# SCH.net
KiCad netlist of a schematic drawn in Altium Designer
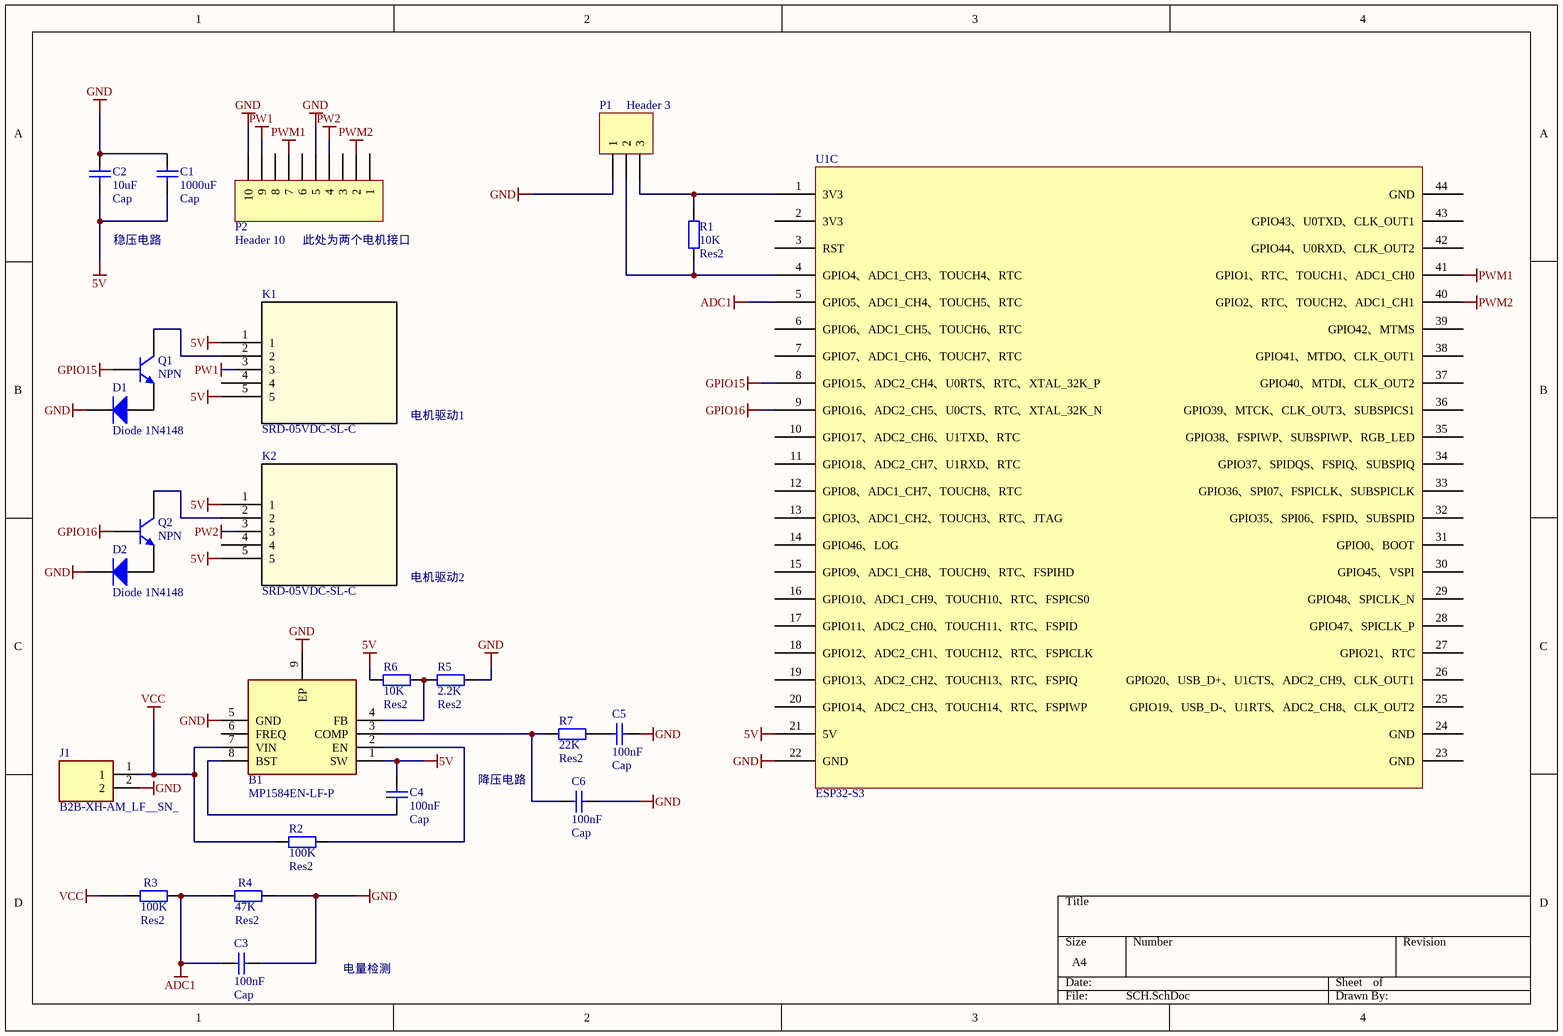
[diagram p0: SCH.SchDoc]

(export (version "E")
  (design (tool "Eeschema 10.0.6"))
  (components
    (comp (ref "B1")
      (value "MP1584EN-LF-P")
      (footprint "SOIC127P600X170-9N")
      (description "Switching Voltage Regulators NRFND: USE MP2338 as replacement")
      (fields (field (name "MOUSER PART NUMBER") "946-MP1584EN-LF-P"))
      (libsource (lib "MP1584EN-LF-P") (part "MP1584EN-LF-P"))
    )
    (comp (ref "C1")
      (value "Cap")
      (footprint "C0805")
      (description "Capacitor")
      (fields (field (name "ALTIUM_VALUE") "1000uF") (field (name "PUBLISHER") "Altium Limited"))
      (libsource (lib "Miscellaneous Devices") (part "Cap"))
    )
    (comp (ref "C2")
      (value "Cap")
      (footprint "C0805")
      (description "Capacitor")
      (fields (field (name "ALTIUM_VALUE") "10uF") (field (name "PUBLISHER") "Altium Limited"))
      (libsource (lib "Miscellaneous Devices") (part "Cap"))
    )
    (comp (ref "C3")
      (value "Cap")
      (footprint "C0805")
      (description "Capacitor")
      (fields (field (name "ALTIUM_VALUE") "100nF") (field (name "PUBLISHER") "Altium Limited"))
      (libsource (lib "Miscellaneous Devices") (part "Cap"))
    )
    (comp (ref "C4")
      (value "Cap")
      (footprint "C0805")
      (description "Capacitor")
      (fields (field (name "ALTIUM_VALUE") "100nF") (field (name "PUBLISHER") "Altium Limited"))
      (libsource (lib "Miscellaneous Devices") (part "Cap"))
    )
    (comp (ref "C5")
      (value "Cap")
      (footprint "C0805")
      (description "Capacitor")
      (fields (field (name "ALTIUM_VALUE") "100nF") (field (name "PUBLISHER") "Altium Limited"))
      (libsource (lib "Miscellaneous Devices") (part "Cap"))
    )
    (comp (ref "C6")
      (value "Cap")
      (footprint "C0805")
      (description "Capacitor")
      (fields (field (name "ALTIUM_VALUE") "100nF") (field (name "PUBLISHER") "Altium Limited"))
      (libsource (lib "Miscellaneous Devices") (part "Cap"))
    )
    (comp (ref "D1")
      (value "Diode 1N4148")
      (footprint "DO-35")
      (description "High Conductance Fast Diode")
      (fields (field (name "PUBLISHER") "Altium Limited"))
      (libsource (lib "Miscellaneous Devices") (part "Diode 1N4148"))
    )
    (comp (ref "D2")
      (value "Diode 1N4148")
      (footprint "DO-35")
      (description "High Conductance Fast Diode")
      (fields (field (name "PUBLISHER") "Altium Limited"))
      (libsource (lib "Miscellaneous Devices") (part "Diode 1N4148"))
    )
    (comp (ref "J1")
      (value "B2B-XH-AM_LF__SN_")
      (footprint "B2BXHAMLFSN")
      (description "CONN HEADER VERT 2POS 2.5MM")
      (fields
        (field (name "MANUFACTURER_PART_NUMBER") "B2B-XH-AM(LF)(SN)")
        (field (name "MOUSER PART NUMBER") "306-B2B-XH-AMLFSNP")
      )
      (libsource (lib "B2B-XH-AM_LF__SN_") (part "B2B-XH-AM_LF__SN_"))
    )
    (comp (ref "K1")
      (value "SRD-05VDC-SL-C")
      (footprint "RELAY_SRD-05VDC-SL-C_MCE")
      (description "Description")
      (fields (field (name "COPYRIGHT") "Copyright (C) 2026 Ultra Librarian. All rights reserved."))
      (libsource (lib "SRD-05VDC-SL-C") (part "SRD-05VDC-SL-C"))
    )
    (comp (ref "K2")
      (value "SRD-05VDC-SL-C")
      (footprint "RELAY_SRD-05VDC-SL-C_MCE")
      (description "Description")
      (fields (field (name "COPYRIGHT") "Copyright (C) 2026 Ultra Librarian. All rights reserved."))
      (libsource (lib "SRD-05VDC-SL-C") (part "SRD-05VDC-SL-C"))
    )
    (comp (ref "P1")
      (value "Header 3")
      (footprint "HDR1X3")
      (description "Header, 3-Pin")
      (fields (field (name "PUBLISHER") "Altium Limited"))
      (libsource (lib "Miscellaneous Connectors") (part "Header 3"))
    )
    (comp (ref "P2")
      (value "Header 10")
      (footprint "HDR1X10")
      (description "Header, 10-Pin")
      (fields (field (name "PUBLISHER") "Altium Limited"))
      (libsource (lib "Miscellaneous Connectors") (part "Header 10"))
    )
    (comp (ref "Q1")
      (value "NPN")
      (footprint "TO-226-AA")
      (description "NPN Bipolar Transistor")
      (fields (field (name "PUBLISHER") "Altium Limited"))
      (libsource (lib "Miscellaneous Devices") (part "NPN"))
    )
    (comp (ref "Q2")
      (value "NPN")
      (footprint "TO-226-AA")
      (description "NPN Bipolar Transistor")
      (fields (field (name "PUBLISHER") "Altium Limited"))
      (libsource (lib "Miscellaneous Devices") (part "NPN"))
    )
    (comp (ref "R1")
      (value "Res2")
      (footprint "C0805")
      (description "Resistor")
      (fields (field (name "ALTIUM_VALUE") "10K") (field (name "PUBLISHER") "Altium Limited"))
      (libsource (lib "") (part "Res2_2"))
    )
    (comp (ref "R2")
      (value "Res2")
      (footprint "C0805")
      (description "Resistor")
      (fields (field (name "ALTIUM_VALUE") "100K") (field (name "PUBLISHER") "Altium Limited"))
      (libsource (lib "") (part "Res2_1"))
    )
    (comp (ref "R3")
      (value "Res2")
      (footprint "C0805")
      (description "Resistor")
      (fields (field (name "ALTIUM_VALUE") "100K") (field (name "PUBLISHER") "Altium Limited"))
      (libsource (lib "") (part "Res2_1"))
    )
    (comp (ref "R4")
      (value "Res2")
      (footprint "C0805")
      (description "Resistor")
      (fields (field (name "ALTIUM_VALUE") "47K") (field (name "PUBLISHER") "Altium Limited"))
      (libsource (lib "") (part "Res2_1"))
    )
    (comp (ref "R5")
      (value "Res2")
      (footprint "C0805")
      (description "Resistor")
      (fields (field (name "ALTIUM_VALUE") "2.2K") (field (name "PUBLISHER") "Altium Limited"))
      (libsource (lib "") (part "Res2_1"))
    )
    (comp (ref "R6")
      (value "Res2")
      (footprint "C0805")
      (description "Resistor")
      (fields (field (name "ALTIUM_VALUE") "10K") (field (name "PUBLISHER") "Altium Limited"))
      (libsource (lib "Miscellaneous Devices") (part "Res2"))
    )
    (comp (ref "R7")
      (value "Res2")
      (footprint "C0805")
      (description "Resistor")
      (fields (field (name "ALTIUM_VALUE") "22K") (field (name "PUBLISHER") "Altium Limited"))
      (libsource (lib "Miscellaneous Devices") (part "Res2"))
    )
    (comp (ref "U1") (value "ESP32-S3") (footprint "ESP32-S3") (libsource (lib "Mylib") (part "ESP32-S3")))
  )
  (nets
    (net (code "1") (name "5V") (class "Default")
      (node (ref "B1") (pin "1") (pinfunction "SW_1") (pintype "passive"))
      (node (ref "C1") (pin "1") (pinfunction "1_1") (pintype "passive"))
      (node (ref "C2") (pin "1") (pinfunction "1_1") (pintype "passive"))
      (node (ref "C4") (pin "1") (pinfunction "1_1") (pintype "passive"))
      (node (ref "K1") (pin "1") (pinfunction "1_1") (pintype "passive"))
      (node (ref "K1") (pin "5") (pinfunction "5_5") (pintype "passive"))
      (node (ref "K2") (pin "1") (pinfunction "1_1") (pintype "passive"))
      (node (ref "K2") (pin "5") (pinfunction "5_5") (pintype "passive"))
      (node (ref "R6") (pin "2") (pinfunction "2_2") (pintype "passive"))
      (node (ref "U1") (pin "21") (pinfunction "5V_21") (pintype "passive"))
    )
    (net (code "2") (name "ADC1") (class "Default")
      (node (ref "C3") (pin "2") (pinfunction "2_2") (pintype "passive"))
      (node (ref "R3") (pin "2") (pinfunction "2_2") (pintype "passive"))
      (node (ref "R4") (pin "1") (pinfunction "1_1") (pintype "passive"))
      (node (ref "U1") (pin "5") (pinfunction "GPIO5、ADC1_CH4、TOUCH5、RTC_5") (pintype "passive"))
    )
    (net (code "3") (name "GND") (class "Default")
      (node (ref "B1") (pin "5") (pinfunction "GND_5") (pintype "passive"))
      (node (ref "B1") (pin "9") (pinfunction "EP_9") (pintype "passive"))
      (node (ref "C1") (pin "2") (pinfunction "2_2") (pintype "passive"))
      (node (ref "C2") (pin "2") (pinfunction "2_2") (pintype "passive"))
      (node (ref "C3") (pin "1") (pinfunction "1_1") (pintype "passive"))
      (node (ref "C5") (pin "1") (pinfunction "1_1") (pintype "passive"))
      (node (ref "C6") (pin "1") (pinfunction "1_1") (pintype "passive"))
      (node (ref "D1") (pin "2") (pinfunction "K_2") (pintype "passive"))
      (node (ref "D2") (pin "2") (pinfunction "K_2") (pintype "passive"))
      (node (ref "J1") (pin "2") (pinfunction "2_2") (pintype "passive"))
      (node (ref "P1") (pin "1") (pinfunction "1_1") (pintype "passive"))
      (node (ref "P2") (pin "10") (pinfunction "10_10") (pintype "passive"))
      (node (ref "P2") (pin "5") (pinfunction "5_5") (pintype "passive"))
      (node (ref "R4") (pin "2") (pinfunction "2_2") (pintype "passive"))
      (node (ref "R5") (pin "2") (pinfunction "2_2") (pintype "passive"))
      (node (ref "U1") (pin "22") (pinfunction "GND_22") (pintype "passive"))
    )
    (net (code "4") (name "GPIO15") (class "Default")
      (node (ref "Q1") (pin "2") (pinfunction "B_2") (pintype "passive"))
      (node (ref "U1") (pin "8") (pinfunction "GPIO15、ADC2_CH4、U0RTS、RTC、XTAL_32K_P_8") (pintype "passive"))
    )
    (net (code "5") (name "GPIO16") (class "Default")
      (node (ref "Q2") (pin "2") (pinfunction "B_2") (pintype "passive"))
      (node (ref "U1") (pin "9") (pinfunction "GPIO16、ADC2_CH5、U0CTS、RTC、XTAL_32K_N_9") (pintype "passive"))
    )
    (net (code "6") (name "Net-(B1-BST)") (class "Default")
      (node (ref "B1") (pin "8") (pinfunction "BST_8") (pintype "passive"))
      (node (ref "C4") (pin "2") (pinfunction "2_2") (pintype "passive"))
    )
    (net (code "7") (name "Net-(B1-COMP)") (class "Default")
      (node (ref "B1") (pin "3") (pinfunction "COMP_3") (pintype "passive"))
      (node (ref "C6") (pin "2") (pinfunction "2_2") (pintype "passive"))
      (node (ref "R7") (pin "2") (pinfunction "2_2") (pintype "passive"))
    )
    (net (code "8") (name "Net-(B1-EN)") (class "Default")
      (node (ref "B1") (pin "2") (pinfunction "EN_2") (pintype "passive"))
      (node (ref "R2") (pin "2") (pinfunction "2_2") (pintype "passive"))
    )
    (net (code "9") (name "Net-(B1-FB)") (class "Default")
      (node (ref "B1") (pin "4") (pinfunction "FB_4") (pintype "passive"))
      (node (ref "R5") (pin "1") (pinfunction "1_1") (pintype "passive"))
      (node (ref "R6") (pin "1") (pinfunction "1_1") (pintype "passive"))
    )
    (net (code "10") (name "Net-(C5-Pad2)") (class "Default")
      (node (ref "C5") (pin "2") (pinfunction "2_2") (pintype "passive"))
      (node (ref "R7") (pin "1") (pinfunction "1_1") (pintype "passive"))
    )
    (net (code "11") (name "Net-(D1-A)") (class "Default")
      (node (ref "D1") (pin "1") (pinfunction "A_1") (pintype "passive"))
      (node (ref "Q1") (pin "3") (pinfunction "E_3") (pintype "passive"))
    )
    (net (code "12") (name "Net-(D2-A)") (class "Default")
      (node (ref "D2") (pin "1") (pinfunction "A_1") (pintype "passive"))
      (node (ref "Q2") (pin "3") (pinfunction "E_3") (pintype "passive"))
    )
    (net (code "13") (name "Net-(P1-Pad3)") (class "Default")
      (node (ref "P1") (pin "3") (pinfunction "3_3") (pintype "passive"))
      (node (ref "R1") (pin "1") (pinfunction "1_1") (pintype "passive"))
      (node (ref "U1") (pin "1") (pinfunction "3V3_1") (pintype "power_in"))
    )
    (net (code "14") (name "Net-(Q1-C)") (class "Default")
      (node (ref "K1") (pin "2") (pinfunction "2_2") (pintype "passive"))
      (node (ref "Q1") (pin "1") (pinfunction "C_1") (pintype "passive"))
    )
    (net (code "15") (name "Net-(Q2-C)") (class "Default")
      (node (ref "K2") (pin "2") (pinfunction "2_2") (pintype "passive"))
      (node (ref "Q2") (pin "1") (pinfunction "C_1") (pintype "passive"))
    )
    (net (code "16") (name "Net-(U1C-GPIO4、ADC1_CH3、TOUCH4、RTC)") (class "Default")
      (node (ref "P1") (pin "2") (pinfunction "2_2") (pintype "passive"))
      (node (ref "R1") (pin "2") (pinfunction "2_2") (pintype "passive"))
      (node (ref "U1") (pin "4") (pinfunction "GPIO4、ADC1_CH3、TOUCH4、RTC_4") (pintype "passive"))
    )
    (net (code "17") (name "PW1") (class "Default")
      (node (ref "K1") (pin "3") (pinfunction "3_3") (pintype "passive"))
      (node (ref "P2") (pin "9") (pinfunction "9_9") (pintype "passive"))
    )
    (net (code "18") (name "PW2") (class "Default")
      (node (ref "K2") (pin "3") (pinfunction "3_3") (pintype "passive"))
      (node (ref "P2") (pin "4") (pinfunction "4_4") (pintype "passive"))
    )
    (net (code "19") (name "PWM1") (class "Default")
      (node (ref "P2") (pin "7") (pinfunction "7_7") (pintype "passive"))
      (node (ref "U1") (pin "41") (pinfunction "GPIO1、RTC、TOUCH1、ADC1_CH0_41") (pintype "passive"))
    )
    (net (code "20") (name "PWM2") (class "Default")
      (node (ref "P2") (pin "2") (pinfunction "2_2") (pintype "passive"))
      (node (ref "U1") (pin "40") (pinfunction "GPIO2、RTC、TOUCH2、ADC1_CH1_40") (pintype "passive"))
    )
    (net (code "21") (name "VCC") (class "Default")
      (node (ref "B1") (pin "7") (pinfunction "VIN_7") (pintype "passive"))
      (node (ref "J1") (pin "1") (pinfunction "1_1") (pintype "passive"))
      (node (ref "R2") (pin "1") (pinfunction "1_1") (pintype "passive"))
      (node (ref "R3") (pin "1") (pinfunction "1_1") (pintype "passive"))
    )
    (net (code "22") (name "unconnected-(B1-FREQ-Pad6)") (class "Default")
      (node (ref "B1") (pin "6") (pinfunction "FREQ_6") (pintype "passive"))
    )
    (net (code "23") (name "unconnected-(K1-Pad4)") (class "Default")
      (node (ref "K1") (pin "4") (pinfunction "4_4") (pintype "passive"))
    )
    (net (code "24") (name "unconnected-(K2-Pad4)") (class "Default")
      (node (ref "K2") (pin "4") (pinfunction "4_4") (pintype "passive"))
    )
    (net (code "25") (name "unconnected-(P2-Pad1)") (class "Default")
      (node (ref "P2") (pin "1") (pinfunction "1_1") (pintype "passive"))
    )
    (net (code "26") (name "unconnected-(P2-Pad3)") (class "Default")
      (node (ref "P2") (pin "3") (pinfunction "3_3") (pintype "passive"))
    )
    (net (code "27") (name "unconnected-(P2-Pad6)") (class "Default")
      (node (ref "P2") (pin "6") (pinfunction "6_6") (pintype "passive"))
    )
    (net (code "28") (name "unconnected-(P2-Pad8)") (class "Default")
      (node (ref "P2") (pin "8") (pinfunction "8_8") (pintype "passive"))
    )
    (net (code "29") (name "unconnected-(U1C-3V3-Pad2)") (class "Default")
      (node (ref "U1") (pin "2") (pinfunction "3V3_2") (pintype "power_in"))
    )
    (net (code "30") (name "unconnected-(U1C-GND-Pad23)") (class "Default")
      (node (ref "U1") (pin "23") (pinfunction "GND_23") (pintype "passive"))
    )
    (net (code "31") (name "unconnected-(U1C-GND-Pad24)") (class "Default")
      (node (ref "U1") (pin "24") (pinfunction "GND_24") (pintype "passive"))
    )
    (net (code "32") (name "unconnected-(U1C-GND-Pad44)") (class "Default")
      (node (ref "U1") (pin "44") (pinfunction "GND_44") (pintype "passive"))
    )
    (net (code "33") (name "unconnected-(U1C-GPIO0、BOOT-Pad31)") (class "Default")
      (node (ref "U1") (pin "31") (pinfunction "GPIO0、BOOT_31") (pintype "passive"))
    )
    (net (code "34") (name "unconnected-(U1C-GPIO3、ADC1_CH2、TOUCH3、RTC、JTAG-Pad13)") (class "Default")
      (node (ref "U1") (pin "13") (pinfunction "GPIO3、ADC1_CH2、TOUCH3、RTC、JTAG_13") (pintype "passive"))
    )
    (net (code "35") (name "unconnected-(U1C-GPIO6、ADC1_CH5、TOUCH6、RTC-Pad6)") (class "Default")
      (node (ref "U1") (pin "6") (pinfunction "GPIO6、ADC1_CH5、TOUCH6、RTC_6") (pintype "passive"))
    )
    (net (code "36") (name "unconnected-(U1C-GPIO7、ADC1_CH6、TOUCH7、RTC-Pad7)") (class "Default")
      (node (ref "U1") (pin "7") (pinfunction "GPIO7、ADC1_CH6、TOUCH7、RTC_7") (pintype "passive"))
    )
    (net (code "37") (name "unconnected-(U1C-GPIO8、ADC1_CH7、TOUCH8、RTC-Pad12)") (class "Default")
      (node (ref "U1") (pin "12") (pinfunction "GPIO8、ADC1_CH7、TOUCH8、RTC_12") (pintype "passive"))
    )
    (net (code "38") (name "unconnected-(U1C-GPIO9、ADC1_CH8、TOUCH9、RTC、FSPIHD-Pad15)") (class "Default")
      (node (ref "U1") (pin "15") (pinfunction "GPIO9、ADC1_CH8、TOUCH9、RTC、FSPIHD_15") (pintype "passive"))
    )
    (net (code "39") (name "unconnected-(U1C-GPIO10、ADC1_CH9、TOUCH10、RTC、FSPICS0-Pad16)") (class "Default")
      (node (ref "U1") (pin "16") (pinfunction "GPIO10、ADC1_CH9、TOUCH10、RTC、FSPICS0_16") (pintype "passive"))
    )
    (net (code "40") (name "unconnected-(U1C-GPIO11、ADC2_CH0、TOUCH11、RTC、FSPID-Pad17)") (class "Default")
      (node (ref "U1") (pin "17") (pinfunction "GPIO11、ADC2_CH0、TOUCH11、RTC、FSPID_17") (pintype "passive"))
    )
    (net (code "41") (name "unconnected-(U1C-GPIO12、ADC2_CH1、TOUCH12、RTC、FSPICLK-Pad18)") (class "Default")
      (node (ref "U1") (pin "18") (pinfunction "GPIO12、ADC2_CH1、TOUCH12、RTC、FSPICLK_18") (pintype "passive"))
    )
    (net (code "42") (name "unconnected-(U1C-GPIO13、ADC2_CH2、TOUCH13、RTC、FSPIQ-Pad19)") (class "Default")
      (node (ref "U1") (pin "19") (pinfunction "GPIO13、ADC2_CH2、TOUCH13、RTC、FSPIQ_19") (pintype "passive"))
    )
    (net (code "43") (name "unconnected-(U1C-GPIO14、ADC2_CH3、TOUCH14、RTC、FSPIWP-Pad20)") (class "Default")
      (node (ref "U1") (pin "20") (pinfunction "GPIO14、ADC2_CH3、TOUCH14、RTC、FSPIWP_20") (pintype "passive"))
    )
    (net (code "44") (name "unconnected-(U1C-GPIO17、ADC2_CH6、U1TXD、RTC-Pad10)") (class "Default")
      (node (ref "U1") (pin "10") (pinfunction "GPIO17、ADC2_CH6、U1TXD、RTC_10") (pintype "passive"))
    )
    (net (code "45") (name "unconnected-(U1C-GPIO18、ADC2_CH7、U1RXD、RTC-Pad11)") (class "Default")
      (node (ref "U1") (pin "11") (pinfunction "GPIO18、ADC2_CH7、U1RXD、RTC_11") (pintype "passive"))
    )
    (net (code "46") (name "unconnected-(U1C-GPIO19、USB_D-、U1RTS、ADC2_CH8、CLK_OUT2-Pad25)") (class "Default")
      (node (ref "U1") (pin "25") (pinfunction "GPIO19、USB_D-、U1RTS、ADC2_CH8、CLK_OUT2_25") (pintype "passive"))
    )
    (net (code "47") (name "unconnected-(U1C-GPIO20、USB_D+、U1CTS、ADC2_CH9、CLK_OUT1-Pad26)") (class "Default")
      (node (ref "U1") (pin "26") (pinfunction "GPIO20、USB_D+、U1CTS、ADC2_CH9、CLK_OUT1_26") (pintype "passive"))
    )
    (net (code "48") (name "unconnected-(U1C-GPIO21、RTC-Pad27)") (class "Default")
      (node (ref "U1") (pin "27") (pinfunction "GPIO21、RTC_27") (pintype "passive"))
    )
    (net (code "49") (name "unconnected-(U1C-GPIO35、SPI06、FSPID、SUBSPID-Pad32)") (class "Default")
      (node (ref "U1") (pin "32") (pinfunction "GPIO35、SPI06、FSPID、SUBSPID_32") (pintype "passive"))
    )
    (net (code "50") (name "unconnected-(U1C-GPIO36、SPI07、FSPICLK、SUBSPICLK-Pad33)") (class "Default")
      (node (ref "U1") (pin "33") (pinfunction "GPIO36、SPI07、FSPICLK、SUBSPICLK_33") (pintype "passive"))
    )
    (net (code "51") (name "unconnected-(U1C-GPIO37、SPIDQS、FSPIQ、SUBSPIQ-Pad34)") (class "Default")
      (node (ref "U1") (pin "34") (pinfunction "GPIO37、SPIDQS、FSPIQ、SUBSPIQ_34") (pintype "passive"))
    )
    (net (code "52") (name "unconnected-(U1C-GPIO38、FSPIWP、SUBSPIWP、RGB_LED-Pad35)") (class "Default")
      (node (ref "U1") (pin "35") (pinfunction "GPIO38、FSPIWP、SUBSPIWP、RGB_LED_35") (pintype "passive"))
    )
    (net (code "53") (name "unconnected-(U1C-GPIO39、MTCK、CLK_OUT3、SUBSPICS1-Pad36)") (class "Default")
      (node (ref "U1") (pin "36") (pinfunction "GPIO39、MTCK、CLK_OUT3、SUBSPICS1_36") (pintype "passive"))
    )
    (net (code "54") (name "unconnected-(U1C-GPIO40、MTDI、CLK_OUT2-Pad37)") (class "Default")
      (node (ref "U1") (pin "37") (pinfunction "GPIO40、MTDI、CLK_OUT2_37") (pintype "passive"))
    )
    (net (code "55") (name "unconnected-(U1C-GPIO41、MTDO、CLK_OUT1-Pad38)") (class "Default")
      (node (ref "U1") (pin "38") (pinfunction "GPIO41、MTDO、CLK_OUT1_38") (pintype "passive"))
    )
    (net (code "56") (name "unconnected-(U1C-GPIO42、MTMS-Pad39)") (class "Default")
      (node (ref "U1") (pin "39") (pinfunction "GPIO42、MTMS_39") (pintype "passive"))
    )
    (net (code "57") (name "unconnected-(U1C-GPIO43、U0TXD、CLK_OUT1-Pad43)") (class "Default")
      (node (ref "U1") (pin "43") (pinfunction "GPIO43、U0TXD、CLK_OUT1_43") (pintype "passive"))
    )
    (net (code "58") (name "unconnected-(U1C-GPIO44、U0RXD、CLK_OUT2-Pad42)") (class "Default")
      (node (ref "U1") (pin "42") (pinfunction "GPIO44、U0RXD、CLK_OUT2_42") (pintype "passive"))
    )
    (net (code "59") (name "unconnected-(U1C-GPIO45、VSPI-Pad30)") (class "Default")
      (node (ref "U1") (pin "30") (pinfunction "GPIO45、VSPI_30") (pintype "passive"))
    )
    (net (code "60") (name "unconnected-(U1C-GPIO46、LOG-Pad14)") (class "Default")
      (node (ref "U1") (pin "14") (pinfunction "GPIO46、LOG_14") (pintype "passive"))
    )
    (net (code "61") (name "unconnected-(U1C-GPIO47、SPICLK_P-Pad28)") (class "Default")
      (node (ref "U1") (pin "28") (pinfunction "GPIO47、SPICLK_P_28") (pintype "passive"))
    )
    (net (code "62") (name "unconnected-(U1C-GPIO48、SPICLK_N-Pad29)") (class "Default")
      (node (ref "U1") (pin "29") (pinfunction "GPIO48、SPICLK_N_29") (pintype "passive"))
    )
    (net (code "63") (name "unconnected-(U1C-RST-Pad3)") (class "Default")
      (node (ref "U1") (pin "3") (pinfunction "RST_3") (pintype "passive"))
    )
  )
)
